# BMP180_breakout.net
KiCad netlist of a schematic drawn in EAGLE
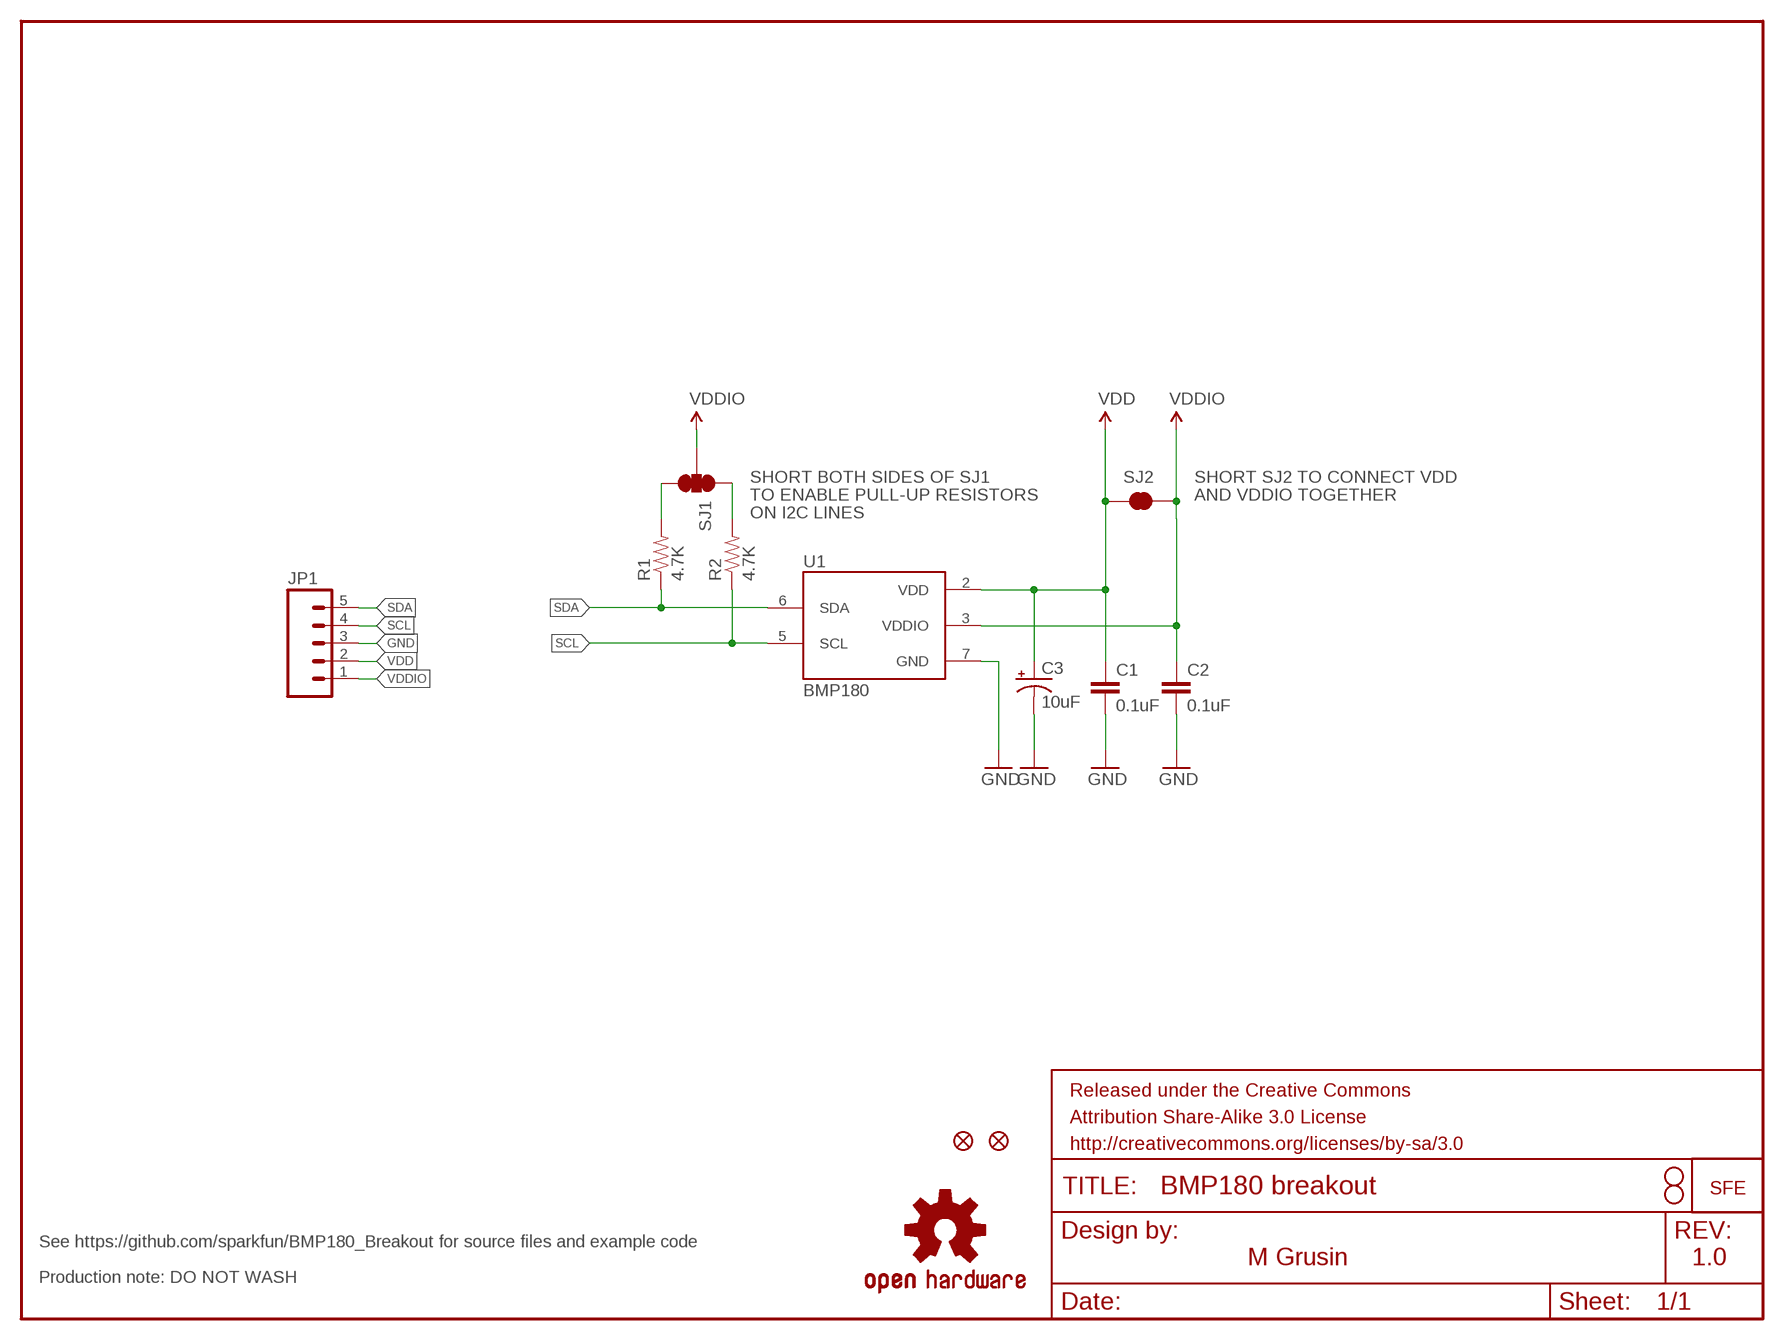
[diagram p0: schematic, sheet 1]

(export (version "E")
  (design (tool "Eeschema 10.0.6"))
  (components
    (comp (ref "C1")
      (value "0.1uF")
      (footprint "eagle-import:0603-CAP")
      (libsource (lib "eagle-import") (part "CAP0603-CAP"))
    )
    (comp (ref "C2")
      (value "0.1uF")
      (footprint "eagle-import:0603-CAP")
      (libsource (lib "eagle-import") (part "CAP0603-CAP"))
    )
    (comp (ref "C3")
      (value "10uF")
      (footprint "eagle-import:EIA3216")
      (libsource (lib "eagle-import") (part "10UF-16V-10%(TANT)"))
    )
    (comp (ref "FID1")
      (value "FIDUCIALUFIDUCIAL")
      (footprint "eagle-import:MICRO-FIDUCIAL")
      (libsource (lib "eagle-import") (part "FIDUCIALUFIDUCIAL"))
    )
    (comp (ref "FID2")
      (value "FIDUCIALUFIDUCIAL")
      (footprint "eagle-import:MICRO-FIDUCIAL")
      (libsource (lib "eagle-import") (part "FIDUCIALUFIDUCIAL"))
    )
    (comp (ref "FRAME1")
      (value "FRAME-LETTER")
      (footprint "eagle-import:CREATIVE_COMMONS")
      (libsource (lib "eagle-import") (part "FRAME-LETTER"))
    )
    (comp (ref "JP1")
      (value "M05_ROUNDONLY_NOSILK")
      (footprint "eagle-import:1X05_ROUNDONLY_NOSILK")
      (libsource (lib "eagle-import") (part "M05_ROUNDONLY_NOSILK"))
    )
    (comp (ref "LOGO1")
      (value "LOGO-SFENW2")
      (footprint "eagle-import:SFE-NEW-WEB")
      (libsource (lib "eagle-import") (part "LOGO-SFENW2"))
    )
    (comp (ref "LOGO2")
      (value "OSHW-LOGOS")
      (footprint "eagle-import:OSHW-LOGO-S")
      (libsource (lib "eagle-import") (part "OSHW-LOGOS"))
    )
    (comp (ref "R1")
      (value "4.7K")
      (footprint "eagle-import:0603-RES")
      (libsource (lib "eagle-import") (part "RESISTOR0603-RES"))
    )
    (comp (ref "R2")
      (value "4.7K")
      (footprint "eagle-import:0603-RES")
      (libsource (lib "eagle-import") (part "RESISTOR0603-RES"))
    )
    (comp (ref "SJ1")
      (value "SOLDERJUMPER_2WAYPASTE1&2&3")
      (footprint "eagle-import:SJ_3_PASTE1&2&3")
      (libsource (lib "eagle-import") (part "SOLDERJUMPER_2WAYPASTE1&2&3"))
    )
    (comp (ref "SJ2")
      (value "SOLDERJUMPERNC")
      (footprint "eagle-import:SJ_2S")
      (libsource (lib "eagle-import") (part "SOLDERJUMPERNC"))
    )
    (comp (ref "STANDOFF1")
      (value "STAND-OFF")
      (footprint "eagle-import:STAND-OFF")
      (libsource (lib "eagle-import") (part "STAND-OFF"))
    )
    (comp (ref "STANDOFF2")
      (value "STAND-OFF")
      (footprint "eagle-import:STAND-OFF")
      (libsource (lib "eagle-import") (part "STAND-OFF"))
    )
    (comp (ref "U1")
      (value "BMP180")
      (footprint "eagle-import:BMP180")
      (libsource (lib "eagle-import") (part "BMP180"))
    )
  )
  (nets
    (net (code "1") (name "GND") (class "Default")
      (node (ref "C1") (pin "2") (pinfunction "2_2") (pintype "passive"))
      (node (ref "C2") (pin "2") (pinfunction "2_2") (pintype "passive"))
      (node (ref "C3") (pin "C") (pinfunction "-_C") (pintype "passive"))
      (node (ref "JP1") (pin "3") (pinfunction "3_3") (pintype "passive"))
      (node (ref "U1") (pin "7") (pinfunction "GND_7") (pintype "power_in"))
    )
    (net (code "2") (name "Net-(R1-Pad2)") (class "Default")
      (node (ref "R1") (pin "2") (pinfunction "2_2") (pintype "passive"))
      (node (ref "SJ1") (pin "3") (pinfunction "3_3") (pintype "passive"))
    )
    (net (code "3") (name "Net-(R2-Pad2)") (class "Default")
      (node (ref "R2") (pin "2") (pinfunction "2_2") (pintype "passive"))
      (node (ref "SJ1") (pin "1") (pinfunction "1_1") (pintype "passive"))
    )
    (net (code "4") (name "SCL") (class "Default")
      (node (ref "JP1") (pin "4") (pinfunction "4_4") (pintype "passive"))
      (node (ref "R2") (pin "1") (pinfunction "1_1") (pintype "passive"))
      (node (ref "U1") (pin "5") (pinfunction "SCL_5") (pintype "input"))
    )
    (net (code "5") (name "SDA") (class "Default")
      (node (ref "JP1") (pin "5") (pinfunction "5_5") (pintype "passive"))
      (node (ref "R1") (pin "1") (pinfunction "1_1") (pintype "passive"))
      (node (ref "U1") (pin "6") (pinfunction "SDA_6") (pintype "bidirectional"))
    )
    (net (code "6") (name "VDD") (class "Default")
      (node (ref "C1") (pin "1") (pinfunction "1_1") (pintype "passive"))
      (node (ref "C3") (pin "A") (pinfunction "+_A") (pintype "passive"))
      (node (ref "JP1") (pin "2") (pinfunction "2_2") (pintype "passive"))
      (node (ref "SJ2") (pin "1") (pinfunction "1_1") (pintype "passive"))
      (node (ref "U1") (pin "2") (pinfunction "VDD_2") (pintype "power_in"))
    )
    (net (code "7") (name "VDDIO") (class "Default")
      (node (ref "C2") (pin "1") (pinfunction "1_1") (pintype "passive"))
      (node (ref "JP1") (pin "1") (pinfunction "1_1") (pintype "passive"))
      (node (ref "SJ1") (pin "2") (pinfunction "2_2") (pintype "passive"))
      (node (ref "SJ2") (pin "2") (pinfunction "2_2") (pintype "passive"))
      (node (ref "U1") (pin "3") (pinfunction "VDDIO_3") (pintype "power_in"))
    )
  )
)
